# CONNECTORS.net
KiCad netlist of a schematic drawn in Altium Designer
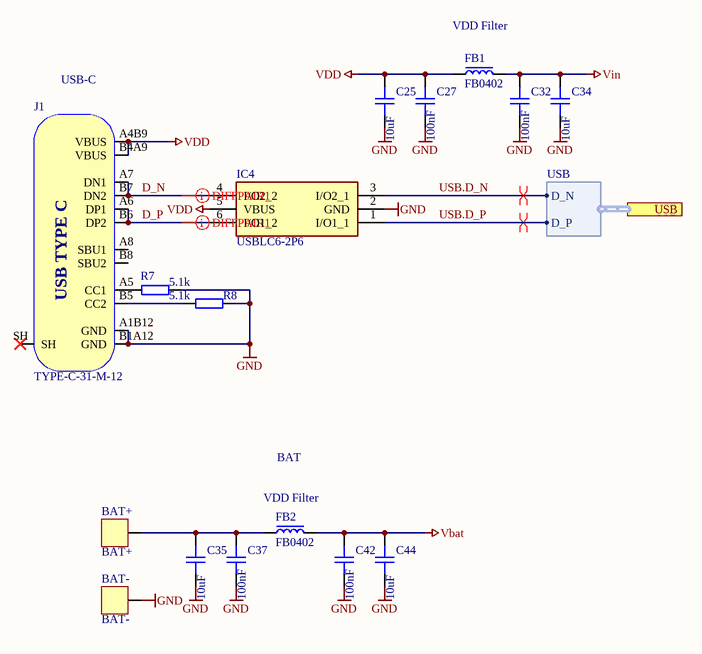
[diagram p0: CONNECTORS.SchDoc]

(export (version "E")
  (design (tool "Eeschema 10.0.6"))
  (components
    (comp (ref "BAT+")
      (value "BAT+")
      (footprint "PAD_SQ_2MM")
      (description "Test Point Square 2mm")
      (libsource (lib "Schematic-Lib-PhilsLab") (part "PAD_SQ_2MM"))
    )
    (comp (ref "BAT-")
      (value "BAT-")
      (footprint "PAD_SQ_2MM")
      (description "Test Point Square 2mm")
      (libsource (lib "Schematic-Lib-PhilsLab") (part "PAD_SQ_2MM"))
    )
    (comp (ref "C25")
      (value "10uF")
      (footprint "CAP_0402")
      (description "Capacitor SMD 0402 10V")
      (fields (field (name "Comment") "C0402_10V"))
      (libsource (lib "Schematic-Lib-PhilsLab") (part "CAP_0402_10V"))
    )
    (comp (ref "C27")
      (value "100nF")
      (footprint "CAP_0402")
      (description "Capacitor SMD 0402 10V")
      (fields (field (name "Comment") "C0402_10V"))
      (libsource (lib "Schematic-Lib-PhilsLab") (part "CAP_0402_10V"))
    )
    (comp (ref "C32")
      (value "100nF")
      (footprint "CAP_0402")
      (description "Capacitor SMD 0402 10V")
      (fields (field (name "Comment") "C0402_10V"))
      (libsource (lib "Schematic-Lib-PhilsLab") (part "CAP_0402_10V"))
    )
    (comp (ref "C34")
      (value "10uF")
      (footprint "CAP_0402")
      (description "Capacitor SMD 0402 10V")
      (fields (field (name "Comment") "C0402_10V"))
      (libsource (lib "Schematic-Lib-PhilsLab") (part "CAP_0402_10V"))
    )
    (comp (ref "C35")
      (value "10uF")
      (footprint "CAP_0402")
      (description "Capacitor SMD 0402 10V")
      (fields (field (name "Comment") "C0402_10V"))
      (libsource (lib "Schematic-Lib-PhilsLab") (part "CAP_0402_10V"))
    )
    (comp (ref "C37")
      (value "100nF")
      (footprint "CAP_0402")
      (description "Capacitor SMD 0402 10V")
      (fields (field (name "Comment") "C0402_10V"))
      (libsource (lib "Schematic-Lib-PhilsLab") (part "CAP_0402_10V"))
    )
    (comp (ref "C42")
      (value "100nF")
      (footprint "CAP_0402")
      (description "Capacitor SMD 0402 10V")
      (fields (field (name "Comment") "C0402_10V"))
      (libsource (lib "Schematic-Lib-PhilsLab") (part "CAP_0402_10V"))
    )
    (comp (ref "C44")
      (value "10uF")
      (footprint "CAP_0402")
      (description "Capacitor SMD 0402 10V")
      (fields (field (name "Comment") "C0402_10V"))
      (libsource (lib "Schematic-Lib-PhilsLab") (part "CAP_0402_10V"))
    )
    (comp (ref "FB1")
      (value "FB0402")
      (footprint "FB_0402")
      (description "Ferrite Bead SMD 0402")
      (libsource (lib "Schematic-Lib-PhilsLab") (part "FB_0402"))
    )
    (comp (ref "FB2")
      (value "FB0402")
      (footprint "FB_0402")
      (description "Ferrite Bead SMD 0402")
      (libsource (lib "Schematic-Lib-PhilsLab") (part "FB_0402"))
    )
    (comp (ref "IC4")
      (value "USBLC6-2P6")
      (footprint "Footprint-Lib-PhilsLab:USBLC62P6")
      (description "Integrated Circuit")
      (fields (field (name "MOUSER PART NUMBER") "511-USBLC6-2P6"))
      (libsource (lib "Schematic-Lib-PhilsLab") (part "USBLC6-2P6"))
    )
    (comp (ref "J1")
      (value "TYPE-C-31-M-12")
      (footprint "TYPE-C-31-M-12")
      (description "USB Type C Connector Horizontal SMT")
      (fields (field (name "MANUFACTURER") "Koren Hroparts"))
      (libsource (lib "Schematic-Lib-PhilsLab") (part "TYPE-C-31-M-12"))
    )
    (comp (ref "R7")
      (value "5.1k")
      (footprint "RES_0402")
      (description "Resistor SMD 0402")
      (fields (field (name "Comment") "R0402"))
      (libsource (lib "Schematic-Lib-PhilsLab") (part "RES_0402"))
    )
    (comp (ref "R8")
      (value "5.1k")
      (footprint "RES_0402")
      (description "Resistor SMD 0402")
      (fields (field (name "Comment") "R0402"))
      (libsource (lib "Schematic-Lib-PhilsLab") (part "RES_0402"))
    )
  )
  (nets
    (net (code "2") (name "/D_N") (class "Default")
      (node (ref "IC4") (pin "4") (pinfunction "I/O2_2_4") (pintype "passive"))
      (node (ref "J1") (pin "A7") (pinfunction "DN1_A7") (pintype "bidirectional"))
      (node (ref "J1") (pin "B7") (pinfunction "DN2_B7") (pintype "bidirectional"))
    )
    (net (code "3") (name "/D_P") (class "Default")
      (node (ref "IC4") (pin "6") (pinfunction "I/O1_2_6") (pintype "passive"))
      (node (ref "J1") (pin "A6") (pinfunction "DP1_A6") (pintype "bidirectional"))
      (node (ref "J1") (pin "B6") (pinfunction "DP2_B6") (pintype "bidirectional"))
    )
    (net (code "4") (name "/USB.D_N") (class "Default")
      (node (ref "IC4") (pin "3") (pinfunction "I/O2_1_3") (pintype "passive"))
    )
    (net (code "5") (name "/USB.D_P") (class "Default")
      (node (ref "IC4") (pin "1") (pinfunction "I/O1_1_1") (pintype "passive"))
    )
    (net (code "7") (name "GND") (class "Default")
      (node (ref "BAT-") (pin "1") (pinfunction "1_1") (pintype "passive"))
      (node (ref "C25") (pin "1") (pinfunction "1_1") (pintype "passive"))
      (node (ref "C27") (pin "1") (pinfunction "1_1") (pintype "passive"))
      (node (ref "C32") (pin "1") (pinfunction "1_1") (pintype "passive"))
      (node (ref "C34") (pin "1") (pinfunction "1_1") (pintype "passive"))
      (node (ref "C35") (pin "1") (pinfunction "1_1") (pintype "passive"))
      (node (ref "C37") (pin "1") (pinfunction "1_1") (pintype "passive"))
      (node (ref "C42") (pin "1") (pinfunction "1_1") (pintype "passive"))
      (node (ref "C44") (pin "1") (pinfunction "1_1") (pintype "passive"))
      (node (ref "IC4") (pin "2") (pinfunction "GND_2") (pintype "passive"))
      (node (ref "J1") (pin "A1B12") (pinfunction "GND_A1B12") (pintype "power_in"))
      (node (ref "J1") (pin "B1A12") (pinfunction "GND_B1A12") (pintype "power_in"))
      (node (ref "R7") (pin "2") (pinfunction "2_2") (pintype "passive"))
      (node (ref "R8") (pin "2") (pinfunction "2_2") (pintype "passive"))
    )
    (net (code "8") (name "Net-(BAT+-Pad1)") (class "Default")
      (node (ref "BAT+") (pin "1") (pinfunction "1_1") (pintype "passive"))
      (node (ref "C35") (pin "2") (pinfunction "2_2") (pintype "passive"))
      (node (ref "C37") (pin "2") (pinfunction "2_2") (pintype "passive"))
      (node (ref "FB2") (pin "1") (pinfunction "1_1") (pintype "passive"))
    )
    (net (code "9") (name "Net-(J1-CC1)") (class "Default")
      (node (ref "J1") (pin "A5") (pinfunction "CC1_A5") (pintype "passive"))
      (node (ref "R7") (pin "1") (pinfunction "1_1") (pintype "passive"))
    )
    (net (code "10") (name "Net-(J1-CC2)") (class "Default")
      (node (ref "J1") (pin "B5") (pinfunction "CC2_B5") (pintype "tri_state"))
      (node (ref "R8") (pin "1") (pinfunction "1_1") (pintype "passive"))
    )
    (net (code "11") (name "VDD") (class "Default")
      (node (ref "C25") (pin "2") (pinfunction "2_2") (pintype "passive"))
      (node (ref "C27") (pin "2") (pinfunction "2_2") (pintype "passive"))
      (node (ref "FB1") (pin "1") (pinfunction "1_1") (pintype "passive"))
      (node (ref "IC4") (pin "5") (pinfunction "VBUS_5") (pintype "passive"))
      (node (ref "J1") (pin "A4B9") (pinfunction "VBUS_A4B9") (pintype "power_in"))
      (node (ref "J1") (pin "B4A9") (pinfunction "VBUS_B4A9") (pintype "power_in"))
    )
    (net (code "12") (name "Vbat") (class "Default")
      (node (ref "C42") (pin "2") (pinfunction "2_2") (pintype "passive"))
      (node (ref "C44") (pin "2") (pinfunction "2_2") (pintype "passive"))
      (node (ref "FB2") (pin "2") (pinfunction "2_2") (pintype "passive"))
    )
    (net (code "13") (name "Vin") (class "Default")
      (node (ref "C32") (pin "2") (pinfunction "2_2") (pintype "passive"))
      (node (ref "C34") (pin "2") (pinfunction "2_2") (pintype "passive"))
      (node (ref "FB1") (pin "2") (pinfunction "2_2") (pintype "passive"))
    )
    (net (code "14") (name "unconnected-(J1-PadSH)") (class "Default")
      (node (ref "J1") (pin "SH") (pinfunction "SH_SH") (pintype "power_in+no_connect"))
    )
    (net (code "15") (name "unconnected-(J1-SBU1-PadA8)") (class "Default")
      (node (ref "J1") (pin "A8") (pinfunction "SBU1_A8") (pintype "bidirectional"))
    )
    (net (code "16") (name "unconnected-(J1-SBU2-PadB8)") (class "Default")
      (node (ref "J1") (pin "B8") (pinfunction "SBU2_B8") (pintype "bidirectional"))
    )
  )
)
